# gestion_batterie.net
KiCad netlist of a schematic drawn in EAGLE
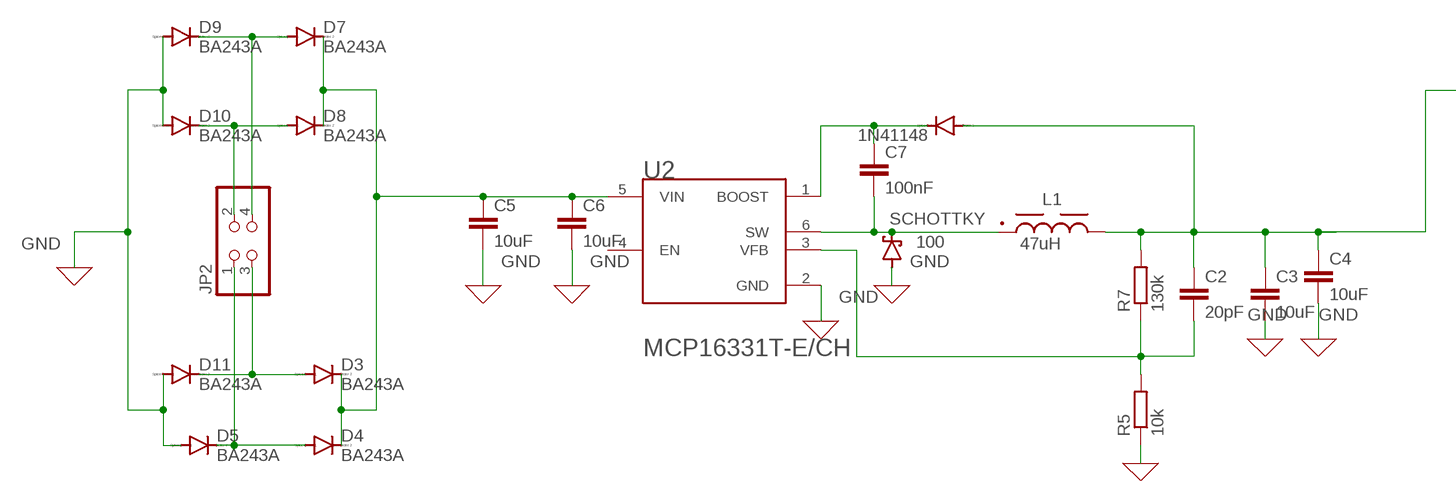
[diagram p0: schematic, sheet 1, part 1 of 2]
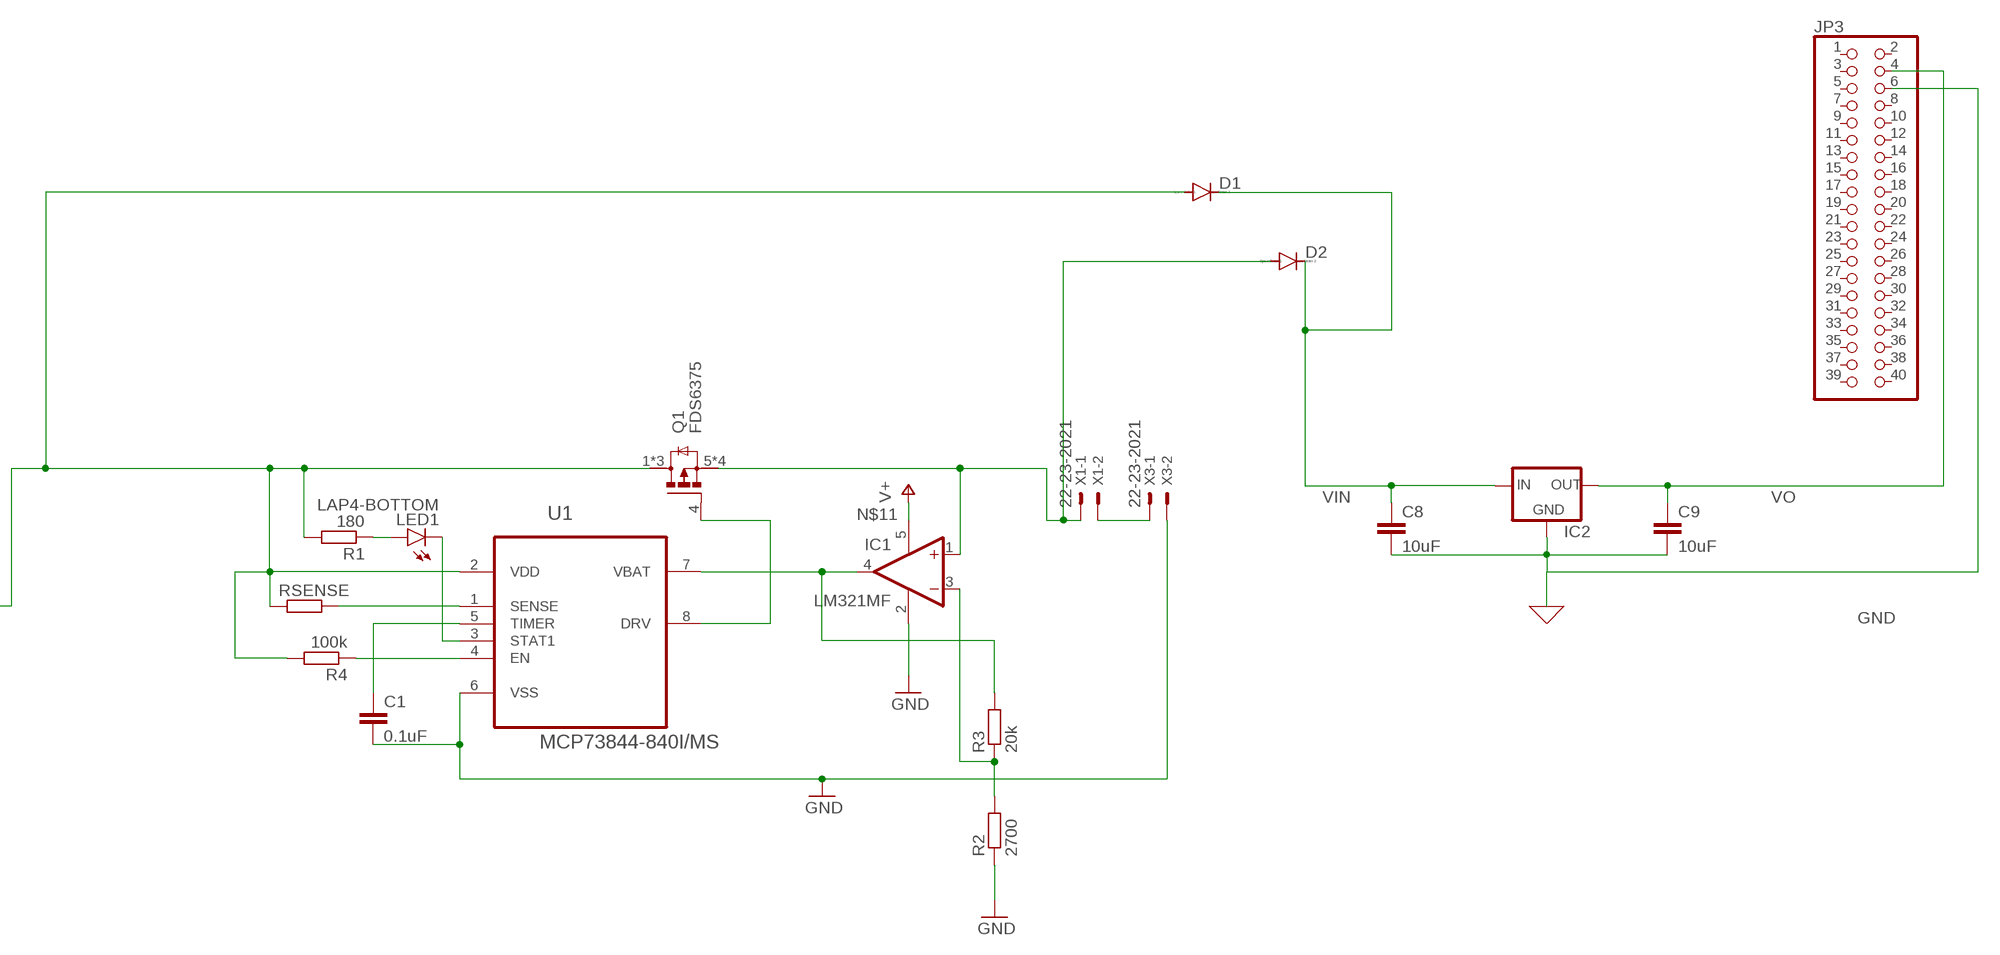
[diagram p1: schematic, sheet 1, part 2 of 2]

(export (version "E")
  (design (tool "Eeschema 10.0.6"))
  (components
    (comp (ref "1N41148")
      (value "DIODE-SOD323-W")
      (footprint "eagle-import:SOD323-W")
      (libsource (lib "eagle-import") (part "DIODE-SOD323-W"))
    )
    (comp (ref "C1")
      (value "0.1uF")
      (footprint "eagle-import:C1206")
      (libsource (lib "eagle-import") (part "C-EUC1206"))
    )
    (comp (ref "C2")
      (value "20pF")
      (footprint "eagle-import:C1206")
      (libsource (lib "eagle-import") (part "C-EUC1206"))
    )
    (comp (ref "C3")
      (value "10uF")
      (footprint "eagle-import:C1206K")
      (libsource (lib "eagle-import") (part "C-EUC1206K"))
    )
    (comp (ref "C4")
      (value "10uF")
      (footprint "eagle-import:C1206K")
      (libsource (lib "eagle-import") (part "C-EUC1206K"))
    )
    (comp (ref "C5")
      (value "10uF")
      (footprint "eagle-import:C1206K")
      (libsource (lib "eagle-import") (part "C-EUC1206K"))
    )
    (comp (ref "C6")
      (value "10uF")
      (footprint "eagle-import:C1206K")
      (libsource (lib "eagle-import") (part "C-EUC1206K"))
    )
    (comp (ref "C7")
      (value "100nF")
      (footprint "eagle-import:C1206")
      (libsource (lib "eagle-import") (part "C-EUC1206"))
    )
    (comp (ref "C8")
      (value "10uF")
      (footprint "eagle-import:C1206K")
      (libsource (lib "eagle-import") (part "C-EUC1206K"))
    )
    (comp (ref "C9")
      (value "10uF")
      (footprint "eagle-import:C1206K")
      (libsource (lib "eagle-import") (part "C-EUC1206K"))
    )
    (comp (ref "D1")
      (value "DIODE-DO201-15")
      (footprint "eagle-import:DO201-15")
      (libsource (lib "eagle-import") (part "DIODE-DO201-15"))
    )
    (comp (ref "D2")
      (value "DIODE-DO201-15")
      (footprint "eagle-import:DO201-15")
      (libsource (lib "eagle-import") (part "DIODE-DO201-15"))
    )
    (comp (ref "D3")
      (value "BA243A")
      (footprint "eagle-import:DO35-10")
      (libsource (lib "eagle-import") (part "BA243A"))
    )
    (comp (ref "D4")
      (value "BA243A")
      (footprint "eagle-import:DO35-10")
      (libsource (lib "eagle-import") (part "BA243A"))
    )
    (comp (ref "D5")
      (value "BA243A")
      (footprint "eagle-import:DO35-10")
      (libsource (lib "eagle-import") (part "BA243A"))
    )
    (comp (ref "D7")
      (value "BA243A")
      (footprint "eagle-import:DO35-10")
      (libsource (lib "eagle-import") (part "BA243A"))
    )
    (comp (ref "D8")
      (value "BA243A")
      (footprint "eagle-import:DO35-10")
      (libsource (lib "eagle-import") (part "BA243A"))
    )
    (comp (ref "D9")
      (value "BA243A")
      (footprint "eagle-import:DO35-10")
      (libsource (lib "eagle-import") (part "BA243A"))
    )
    (comp (ref "D10")
      (value "BA243A")
      (footprint "eagle-import:DO35-10")
      (libsource (lib "eagle-import") (part "BA243A"))
    )
    (comp (ref "D11")
      (value "BA243A")
      (footprint "eagle-import:DO35-10")
      (libsource (lib "eagle-import") (part "BA243A"))
    )
    (comp (ref "IC1")
      (value "LM321MF")
      (footprint "eagle-import:SOT23-5")
      (libsource (lib "eagle-import") (part "LM321?MF"))
    )
    (comp (ref "IC2")
      (value "78MXXL")
      (footprint "eagle-import:78MXXL")
      (libsource (lib "eagle-import") (part "78MXXL"))
    )
    (comp (ref "JP2")
      (value "PINHD-2X2")
      (footprint "eagle-import:2X02")
      (libsource (lib "eagle-import") (part "PINHD-2X2"))
    )
    (comp (ref "JP3")
      (value "PINHD-2X20")
      (footprint "eagle-import:2X20")
      (libsource (lib "eagle-import") (part "PINHD-2X20"))
    )
    (comp (ref "L1")
      (value "47uH")
      (footprint "eagle-import:WE-PDA_1210")
      (libsource (lib "eagle-import") (part "WE-PDA_1210_7847709470"))
    )
    (comp (ref "LED1")
      (value "LAP4-BOTTOM")
      (footprint "eagle-import:P47F-BOTTOM")
      (libsource (lib "eagle-import") (part "P4-BOTTOMLA"))
    )
    (comp (ref "Q1")
      (value "FDS6375")
      (footprint "eagle-import:SOIC127P600X175-8N")
      (fields (field (name "MF") "ON Semiconductor"))
      (libsource (lib "eagle-import") (part "FDS6375"))
    )
    (comp (ref "R1")
      (value "180")
      (footprint "eagle-import:R1206")
      (libsource (lib "eagle-import") (part "R-EU_R1206"))
    )
    (comp (ref "R2")
      (value "2700")
      (footprint "eagle-import:R1206")
      (libsource (lib "eagle-import") (part "R-EU_R1206"))
    )
    (comp (ref "R3")
      (value "20k")
      (footprint "eagle-import:R1206")
      (libsource (lib "eagle-import") (part "R-EU_R1206"))
    )
    (comp (ref "R4")
      (value "100k")
      (footprint "eagle-import:R1206")
      (libsource (lib "eagle-import") (part "R-EU_R1206"))
    )
    (comp (ref "R5")
      (value "10k")
      (footprint "eagle-import:R1206")
      (libsource (lib "eagle-import") (part "R-EU_R1206"))
    )
    (comp (ref "R7")
      (value "130k")
      (footprint "eagle-import:R1206")
      (libsource (lib "eagle-import") (part "R-EU_R1206"))
    )
    (comp (ref "RSENSE")
      (value "R-EU_R1210")
      (footprint "eagle-import:R1210")
      (libsource (lib "eagle-import") (part "R-EU_R1210"))
    )
    (comp (ref "SCHOTTKY")
      (value "100")
      (footprint "eagle-import:CB417-15")
      (libsource (lib "eagle-import") (part "SCHOTTKY-DIODECB417-15"))
    )
    (comp (ref "U1")
      (value "MCP73844-840I/MS")
      (footprint "eagle-import:SOP65P490X110-8N")
      (libsource (lib "eagle-import") (part "MCP73844-840I/MS"))
    )
    (comp (ref "U2")
      (value "MICROCHIP_MCP16331T-E-CHMICROCHIP_MCP16331T-E-CH_0_0")
      (footprint "eagle-import:MICROCHIP_MCP16331T-E-CH_0")
      (fields
        (field (name "DIGIKEY_PART_NUMBER") "MCP16331T-E/CHCT-ND")
        (field (name "MF") "Microchip")
        (field (name "MOUSER_PART_NUMBER") "579-MCP16331T-E/CH")
      )
      (libsource (lib "eagle-import") (part "MICROCHIP_MCP16331T-E-CHMICROCHIP_MCP16331T-E-CH_0_0"))
    )
    (comp (ref "X1")
      (value "22-23-2021")
      (footprint "eagle-import:22-23-2021")
      (fields (field (name "MF") "MOLEX"))
      (libsource (lib "eagle-import") (part "22-23-2021"))
    )
    (comp (ref "X3")
      (value "22-23-2021")
      (footprint "eagle-import:22-23-2021")
      (fields (field (name "MF") "MOLEX"))
      (libsource (lib "eagle-import") (part "22-23-2021"))
    )
  )
  (nets
    (net (code "1") (name "/VIN") (class "Default")
      (node (ref "C8") (pin "1") (pinfunction "1_1") (pintype "passive"))
      (node (ref "D1") (pin "C") (pinfunction "C_C") (pintype "passive"))
      (node (ref "D2") (pin "C") (pinfunction "C_C") (pintype "passive"))
      (node (ref "IC2") (pin "IN") (pinfunction "IN_IN") (pintype "input"))
    )
    (net (code "2") (name "/VO") (class "Default")
      (node (ref "C9") (pin "1") (pinfunction "1_1") (pintype "passive"))
      (node (ref "IC2") (pin "OUT") (pinfunction "OUT_OUT") (pintype "passive"))
      (node (ref "JP3") (pin "4") (pinfunction "4_4") (pintype "passive"))
    )
    (net (code "3") (name "GND") (class "Default")
      (node (ref "C1") (pin "2") (pinfunction "2_2") (pintype "passive"))
      (node (ref "C3") (pin "2") (pinfunction "2_2") (pintype "passive"))
      (node (ref "C4") (pin "2") (pinfunction "2_2") (pintype "passive"))
      (node (ref "C5") (pin "2") (pinfunction "2_2") (pintype "passive"))
      (node (ref "C6") (pin "2") (pinfunction "2_2") (pintype "passive"))
      (node (ref "C8") (pin "2") (pinfunction "2_2") (pintype "passive"))
      (node (ref "C9") (pin "2") (pinfunction "2_2") (pintype "passive"))
      (node (ref "D10") (pin "A") (pinfunction "A_A") (pintype "passive"))
      (node (ref "D11") (pin "A") (pinfunction "A_A") (pintype "passive"))
      (node (ref "D5") (pin "A") (pinfunction "A_A") (pintype "passive"))
      (node (ref "D9") (pin "A") (pinfunction "A_A") (pintype "passive"))
      (node (ref "IC1") (pin "2") (pinfunction "V-_2") (pintype "power_in"))
      (node (ref "IC2") (pin "GND") (pinfunction "GND_GND") (pintype "input"))
      (node (ref "JP3") (pin "6") (pinfunction "6_6") (pintype "passive"))
      (node (ref "R2") (pin "1") (pinfunction "1_1") (pintype "passive"))
      (node (ref "R5") (pin "1") (pinfunction "1_1") (pintype "passive"))
      (node (ref "SCHOTTKY") (pin "A") (pinfunction "A_A") (pintype "passive"))
      (node (ref "U1") (pin "6") (pinfunction "VSS_6") (pintype "power_in"))
      (node (ref "U2") (pin "2") (pinfunction "GND_2") (pintype "bidirectional"))
      (node (ref "X3") (pin "2") (pinfunction "S_2") (pintype "passive"))
    )
    (net (code "4") (name "Net-(D4-PadA)") (class "Default")
      (node (ref "D4") (pin "A") (pinfunction "A_A") (pintype "passive"))
      (node (ref "D5") (pin "C") (pinfunction "C_C") (pintype "passive"))
      (node (ref "JP2") (pin "1") (pinfunction "1_1") (pintype "passive"))
    )
    (net (code "5") (name "Net-(D7-PadA)") (class "Default")
      (node (ref "D7") (pin "A") (pinfunction "A_A") (pintype "passive"))
      (node (ref "D9") (pin "C") (pinfunction "C_C") (pintype "passive"))
      (node (ref "JP2") (pin "4") (pinfunction "4_4") (pintype "passive"))
    )
    (net (code "6") (name "Net-(D10-PadC)") (class "Default")
      (node (ref "D10") (pin "C") (pinfunction "C_C") (pintype "passive"))
      (node (ref "D8") (pin "A") (pinfunction "A_A") (pintype "passive"))
      (node (ref "JP2") (pin "2") (pinfunction "2_2") (pintype "passive"))
    )
    (net (code "7") (name "Net-(D11-PadC)") (class "Default")
      (node (ref "D11") (pin "C") (pinfunction "C_C") (pintype "passive"))
      (node (ref "D3") (pin "A") (pinfunction "A_A") (pintype "passive"))
      (node (ref "JP2") (pin "3") (pinfunction "3_3") (pintype "passive"))
    )
    (net (code "8") (name "Net-(IC1-+IN)") (class "Default")
      (node (ref "D2") (pin "A") (pinfunction "A_A") (pintype "passive"))
      (node (ref "IC1") (pin "1") (pinfunction "+IN_1") (pintype "input"))
      (node (ref "Q1") (pin "5") (pinfunction "D_5") (pintype "passive"))
      (node (ref "Q1") (pin "6") (pinfunction "D_6") (pintype "passive"))
      (node (ref "Q1") (pin "7") (pinfunction "D_7") (pintype "passive"))
      (node (ref "Q1") (pin "8") (pinfunction "D_8") (pintype "passive"))
      (node (ref "X1") (pin "1") (pinfunction "S_1") (pintype "passive"))
    )
    (net (code "9") (name "Net-(IC1--IN)") (class "Default")
      (node (ref "IC1") (pin "3") (pinfunction "-IN_3") (pintype "input"))
      (node (ref "R2") (pin "2") (pinfunction "2_2") (pintype "passive"))
      (node (ref "R3") (pin "1") (pinfunction "1_1") (pintype "passive"))
    )
    (net (code "10") (name "Net-(IC1-OUT)") (class "Default")
      (node (ref "IC1") (pin "4") (pinfunction "OUT_4") (pintype "output"))
      (node (ref "R3") (pin "2") (pinfunction "2_2") (pintype "passive"))
      (node (ref "U1") (pin "7") (pinfunction "VBAT_7") (pintype "output"))
    )
    (net (code "11") (name "Net-(LED1-PadA)") (class "Default")
      (node (ref "LED1") (pin "A") (pinfunction "A_A") (pintype "passive"))
      (node (ref "R1") (pin "1") (pinfunction "1_1") (pintype "passive"))
    )
    (net (code "12") (name "Net-(Q1-G)") (class "Default")
      (node (ref "Q1") (pin "4") (pinfunction "G_4") (pintype "passive"))
      (node (ref "U1") (pin "8") (pinfunction "DRV_8") (pintype "output"))
    )
    (net (code "13") (name "Net-(U1-EN)") (class "Default")
      (node (ref "R4") (pin "1") (pinfunction "1_1") (pintype "passive"))
      (node (ref "U1") (pin "4") (pinfunction "EN_4") (pintype "input"))
    )
    (net (code "14") (name "Net-(U1-SENSE)") (class "Default")
      (node (ref "RSENSE") (pin "2") (pinfunction "2_2") (pintype "passive"))
      (node (ref "U1") (pin "1") (pinfunction "SENSE_1") (pintype "input"))
    )
    (net (code "15") (name "Net-(U1-STAT1)") (class "Default")
      (node (ref "LED1") (pin "C") (pinfunction "C_C") (pintype "passive"))
      (node (ref "U1") (pin "3") (pinfunction "STAT1_3") (pintype "input"))
    )
    (net (code "16") (name "Net-(U1-TIMER)") (class "Default")
      (node (ref "C1") (pin "1") (pinfunction "1_1") (pintype "passive"))
      (node (ref "U1") (pin "5") (pinfunction "TIMER_5") (pintype "input"))
    )
    (net (code "17") (name "Net-(U1-VDD)") (class "Default")
      (node (ref "1N41148") (pin "A") (pinfunction "A_A") (pintype "passive"))
      (node (ref "C2") (pin "1") (pinfunction "1_1") (pintype "passive"))
      (node (ref "C3") (pin "1") (pinfunction "1_1") (pintype "passive"))
      (node (ref "C4") (pin "1") (pinfunction "1_1") (pintype "passive"))
      (node (ref "D1") (pin "A") (pinfunction "A_A") (pintype "passive"))
      (node (ref "L1") (pin "2") (pinfunction "2_2") (pintype "passive"))
      (node (ref "Q1") (pin "1") (pinfunction "S_1") (pintype "passive"))
      (node (ref "Q1") (pin "2") (pinfunction "S_2") (pintype "passive"))
      (node (ref "Q1") (pin "3") (pinfunction "S_3") (pintype "passive"))
      (node (ref "R1") (pin "2") (pinfunction "2_2") (pintype "passive"))
      (node (ref "R4") (pin "2") (pinfunction "2_2") (pintype "passive"))
      (node (ref "R7") (pin "2") (pinfunction "2_2") (pintype "passive"))
      (node (ref "RSENSE") (pin "1") (pinfunction "1_1") (pintype "passive"))
      (node (ref "U1") (pin "2") (pinfunction "VDD_2") (pintype "power_in"))
    )
    (net (code "18") (name "Net-(U2-BOOST)") (class "Default")
      (node (ref "1N41148") (pin "C") (pinfunction "C_C") (pintype "passive"))
      (node (ref "C7") (pin "1") (pinfunction "1_1") (pintype "passive"))
      (node (ref "U2") (pin "1") (pinfunction "BOOST_1") (pintype "bidirectional"))
    )
    (net (code "19") (name "Net-(U2-SW)") (class "Default")
      (node (ref "C7") (pin "2") (pinfunction "2_2") (pintype "passive"))
      (node (ref "L1") (pin "1") (pinfunction "1_1") (pintype "passive"))
      (node (ref "SCHOTTKY") (pin "C") (pinfunction "C_C") (pintype "passive"))
      (node (ref "U2") (pin "6") (pinfunction "SW_6") (pintype "bidirectional"))
    )
    (net (code "20") (name "Net-(U2-VFB)") (class "Default")
      (node (ref "C2") (pin "2") (pinfunction "2_2") (pintype "passive"))
      (node (ref "R5") (pin "2") (pinfunction "2_2") (pintype "passive"))
      (node (ref "R7") (pin "1") (pinfunction "1_1") (pintype "passive"))
      (node (ref "U2") (pin "3") (pinfunction "VFB_3") (pintype "bidirectional"))
    )
    (net (code "21") (name "Net-(X1B-S)") (class "Default")
      (node (ref "X1") (pin "2") (pinfunction "S_2") (pintype "passive"))
      (node (ref "X3") (pin "1") (pinfunction "S_1") (pintype "passive"))
    )
    (net (code "22") (name "V+") (class "Default")
      (node (ref "C5") (pin "1") (pinfunction "1_1") (pintype "passive"))
      (node (ref "C6") (pin "1") (pinfunction "1_1") (pintype "passive"))
      (node (ref "D3") (pin "C") (pinfunction "C_C") (pintype "passive"))
      (node (ref "D4") (pin "C") (pinfunction "C_C") (pintype "passive"))
      (node (ref "D7") (pin "C") (pinfunction "C_C") (pintype "passive"))
      (node (ref "D8") (pin "C") (pinfunction "C_C") (pintype "passive"))
      (node (ref "IC1") (pin "5") (pinfunction "V+_5") (pintype "power_in"))
      (node (ref "U2") (pin "5") (pinfunction "VIN_5") (pintype "bidirectional"))
    )
    (net (code "23") (name "unconnected-(JP3-Pad1)") (class "Default")
      (node (ref "JP3") (pin "1") (pinfunction "1_1") (pintype "passive"))
    )
    (net (code "24") (name "unconnected-(JP3-Pad2)") (class "Default")
      (node (ref "JP3") (pin "2") (pinfunction "2_2") (pintype "passive"))
    )
    (net (code "25") (name "unconnected-(JP3-Pad3)") (class "Default")
      (node (ref "JP3") (pin "3") (pinfunction "3_3") (pintype "passive"))
    )
    (net (code "26") (name "unconnected-(JP3-Pad5)") (class "Default")
      (node (ref "JP3") (pin "5") (pinfunction "5_5") (pintype "passive"))
    )
    (net (code "27") (name "unconnected-(JP3-Pad7)") (class "Default")
      (node (ref "JP3") (pin "7") (pinfunction "7_7") (pintype "passive"))
    )
    (net (code "28") (name "unconnected-(JP3-Pad8)") (class "Default")
      (node (ref "JP3") (pin "8") (pinfunction "8_8") (pintype "passive"))
    )
    (net (code "29") (name "unconnected-(JP3-Pad9)") (class "Default")
      (node (ref "JP3") (pin "9") (pinfunction "9_9") (pintype "passive"))
    )
    (net (code "30") (name "unconnected-(JP3-Pad10)") (class "Default")
      (node (ref "JP3") (pin "10") (pinfunction "10_10") (pintype "passive"))
    )
    (net (code "31") (name "unconnected-(JP3-Pad11)") (class "Default")
      (node (ref "JP3") (pin "11") (pinfunction "11_11") (pintype "passive"))
    )
    (net (code "32") (name "unconnected-(JP3-Pad12)") (class "Default")
      (node (ref "JP3") (pin "12") (pinfunction "12_12") (pintype "passive"))
    )
    (net (code "33") (name "unconnected-(JP3-Pad13)") (class "Default")
      (node (ref "JP3") (pin "13") (pinfunction "13_13") (pintype "passive"))
    )
    (net (code "34") (name "unconnected-(JP3-Pad14)") (class "Default")
      (node (ref "JP3") (pin "14") (pinfunction "14_14") (pintype "passive"))
    )
    (net (code "35") (name "unconnected-(JP3-Pad15)") (class "Default")
      (node (ref "JP3") (pin "15") (pinfunction "15_15") (pintype "passive"))
    )
    (net (code "36") (name "unconnected-(JP3-Pad16)") (class "Default")
      (node (ref "JP3") (pin "16") (pinfunction "16_16") (pintype "passive"))
    )
    (net (code "37") (name "unconnected-(JP3-Pad17)") (class "Default")
      (node (ref "JP3") (pin "17") (pinfunction "17_17") (pintype "passive"))
    )
    (net (code "38") (name "unconnected-(JP3-Pad18)") (class "Default")
      (node (ref "JP3") (pin "18") (pinfunction "18_18") (pintype "passive"))
    )
    (net (code "39") (name "unconnected-(JP3-Pad19)") (class "Default")
      (node (ref "JP3") (pin "19") (pinfunction "19_19") (pintype "passive"))
    )
    (net (code "40") (name "unconnected-(JP3-Pad20)") (class "Default")
      (node (ref "JP3") (pin "20") (pinfunction "20_20") (pintype "passive"))
    )
    (net (code "41") (name "unconnected-(JP3-Pad21)") (class "Default")
      (node (ref "JP3") (pin "21") (pinfunction "21_21") (pintype "passive"))
    )
    (net (code "42") (name "unconnected-(JP3-Pad22)") (class "Default")
      (node (ref "JP3") (pin "22") (pinfunction "22_22") (pintype "passive"))
    )
    (net (code "43") (name "unconnected-(JP3-Pad23)") (class "Default")
      (node (ref "JP3") (pin "23") (pinfunction "23_23") (pintype "passive"))
    )
    (net (code "44") (name "unconnected-(JP3-Pad24)") (class "Default")
      (node (ref "JP3") (pin "24") (pinfunction "24_24") (pintype "passive"))
    )
    (net (code "45") (name "unconnected-(JP3-Pad25)") (class "Default")
      (node (ref "JP3") (pin "25") (pinfunction "25_25") (pintype "passive"))
    )
    (net (code "46") (name "unconnected-(JP3-Pad26)") (class "Default")
      (node (ref "JP3") (pin "26") (pinfunction "26_26") (pintype "passive"))
    )
    (net (code "47") (name "unconnected-(JP3-Pad27)") (class "Default")
      (node (ref "JP3") (pin "27") (pinfunction "27_27") (pintype "passive"))
    )
    (net (code "48") (name "unconnected-(JP3-Pad28)") (class "Default")
      (node (ref "JP3") (pin "28") (pinfunction "28_28") (pintype "passive"))
    )
    (net (code "49") (name "unconnected-(JP3-Pad29)") (class "Default")
      (node (ref "JP3") (pin "29") (pinfunction "29_29") (pintype "passive"))
    )
    (net (code "50") (name "unconnected-(JP3-Pad30)") (class "Default")
      (node (ref "JP3") (pin "30") (pinfunction "30_30") (pintype "passive"))
    )
    (net (code "51") (name "unconnected-(JP3-Pad31)") (class "Default")
      (node (ref "JP3") (pin "31") (pinfunction "31_31") (pintype "passive"))
    )
    (net (code "52") (name "unconnected-(JP3-Pad32)") (class "Default")
      (node (ref "JP3") (pin "32") (pinfunction "32_32") (pintype "passive"))
    )
    (net (code "53") (name "unconnected-(JP3-Pad33)") (class "Default")
      (node (ref "JP3") (pin "33") (pinfunction "33_33") (pintype "passive"))
    )
    (net (code "54") (name "unconnected-(JP3-Pad34)") (class "Default")
      (node (ref "JP3") (pin "34") (pinfunction "34_34") (pintype "passive"))
    )
    (net (code "55") (name "unconnected-(JP3-Pad35)") (class "Default")
      (node (ref "JP3") (pin "35") (pinfunction "35_35") (pintype "passive"))
    )
    (net (code "56") (name "unconnected-(JP3-Pad36)") (class "Default")
      (node (ref "JP3") (pin "36") (pinfunction "36_36") (pintype "passive"))
    )
    (net (code "57") (name "unconnected-(JP3-Pad37)") (class "Default")
      (node (ref "JP3") (pin "37") (pinfunction "37_37") (pintype "passive"))
    )
    (net (code "58") (name "unconnected-(JP3-Pad38)") (class "Default")
      (node (ref "JP3") (pin "38") (pinfunction "38_38") (pintype "passive"))
    )
    (net (code "59") (name "unconnected-(JP3-Pad39)") (class "Default")
      (node (ref "JP3") (pin "39") (pinfunction "39_39") (pintype "passive"))
    )
    (net (code "60") (name "unconnected-(JP3-Pad40)") (class "Default")
      (node (ref "JP3") (pin "40") (pinfunction "40_40") (pintype "passive"))
    )
    (net (code "61") (name "unconnected-(U2-EN-Pad4)") (class "Default")
      (node (ref "U2") (pin "4") (pinfunction "EN_4") (pintype "bidirectional"))
    )
  )
)
